# schematic.net
KiCad netlist of a schematic drawn in EAGLE
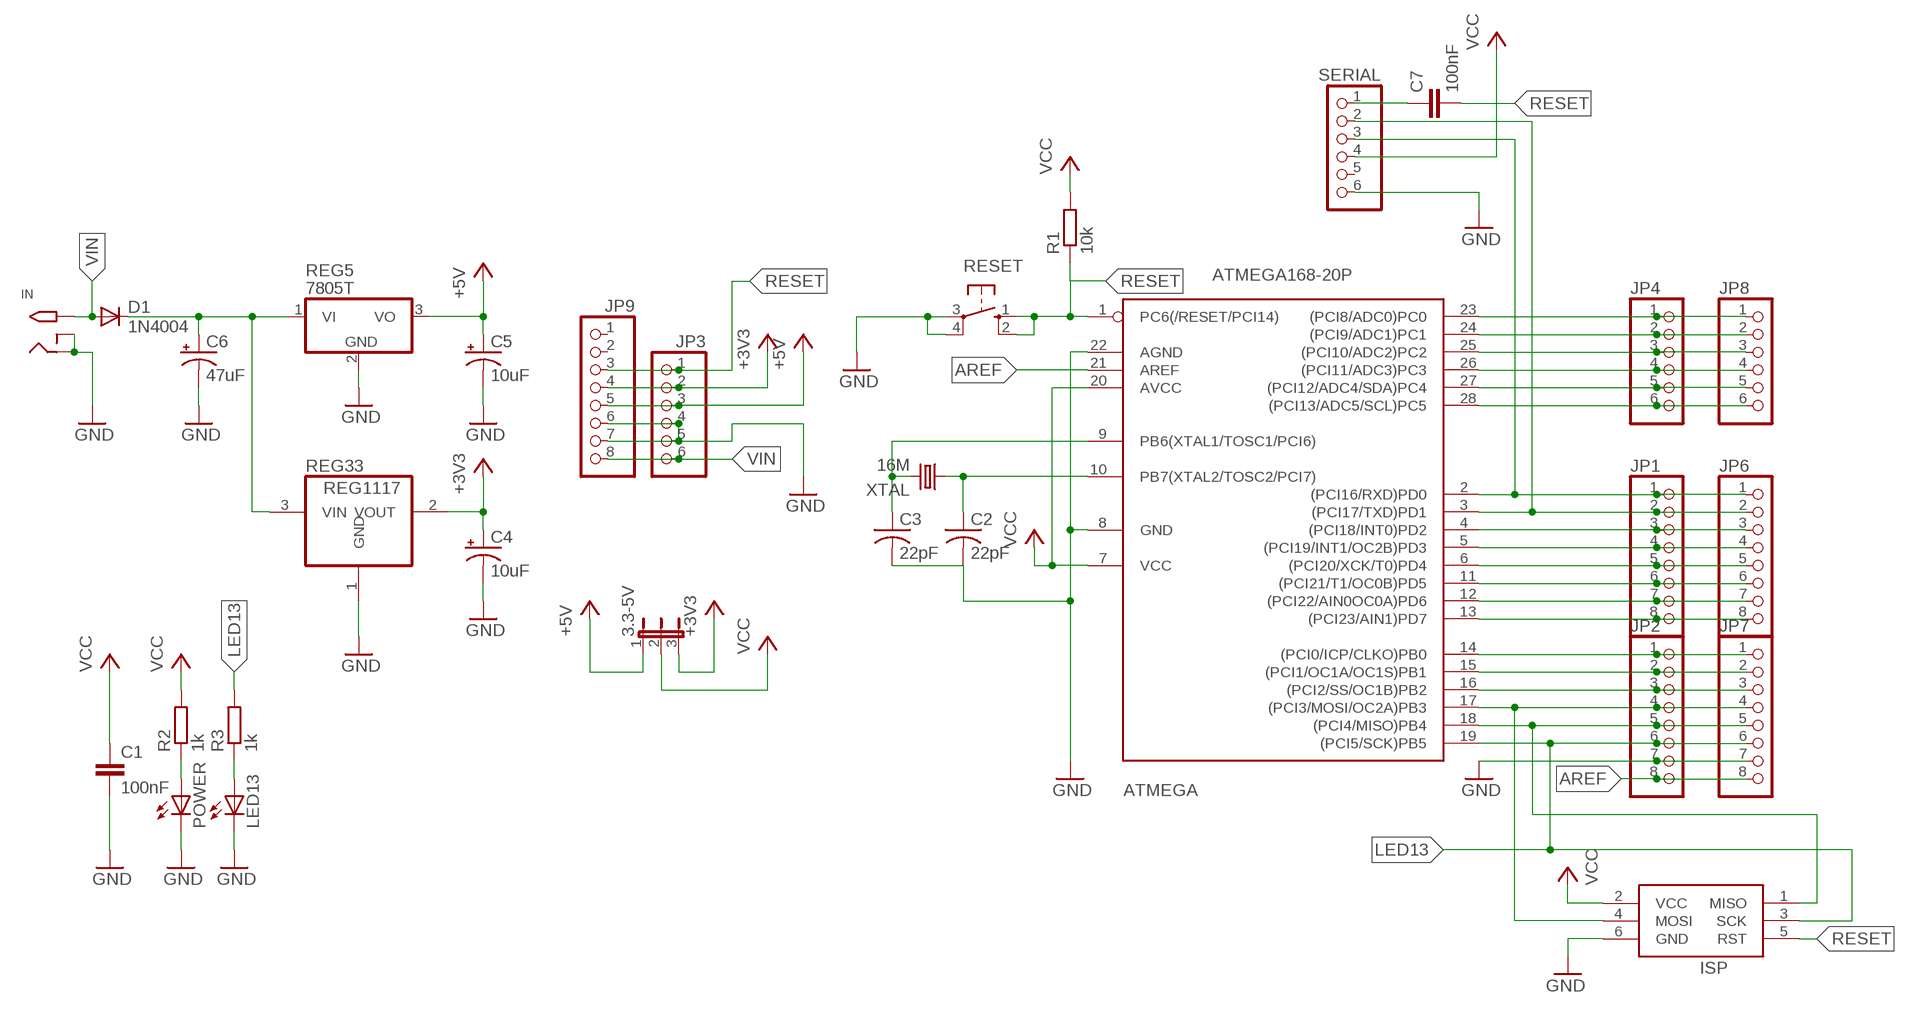
[diagram p0: schematic, sheet 1]

(export (version "E")
  (design (tool "Eeschema 10.0.6"))
  (components
    (comp (ref "3.3-5V")
      (value "JP2E")
      (footprint "eagle-import:JP2")
      (libsource (lib "eagle-import") (part "JP2E"))
    )
    (comp (ref "ATMEGA")
      (value "ATMEGA168-20P")
      (footprint "eagle-import:DIL28-3")
      (libsource (lib "eagle-import") (part "ATMEGA168P-20"))
    )
    (comp (ref "C1")
      (value "100nF")
      (footprint "eagle-import:C050-025X075")
      (libsource (lib "eagle-import") (part "C-EU050-025X075"))
    )
    (comp (ref "C2")
      (value "22pF")
      (footprint "eagle-import:C025-030X050")
      (libsource (lib "eagle-import") (part "C-US025-030X050"))
    )
    (comp (ref "C3")
      (value "22pF")
      (footprint "eagle-import:C025-030X050")
      (libsource (lib "eagle-import") (part "C-US025-030X050"))
    )
    (comp (ref "C4")
      (value "10uF")
      (footprint "eagle-import:E2,5-5")
      (libsource (lib "eagle-import") (part "CPOL-USE2.5-5"))
    )
    (comp (ref "C5")
      (value "10uF")
      (footprint "eagle-import:E2,5-5")
      (libsource (lib "eagle-import") (part "CPOL-USE2.5-5"))
    )
    (comp (ref "C6")
      (value "47uF")
      (footprint "eagle-import:E2,5-6")
      (libsource (lib "eagle-import") (part "CPOL-USE2.5-6"))
    )
    (comp (ref "C7")
      (value "100nF")
      (footprint "eagle-import:C050-025X075")
      (libsource (lib "eagle-import") (part "C-EU050-025X075"))
    )
    (comp (ref "D1")
      (value "1N4004")
      (footprint "eagle-import:DO41-10")
      (libsource (lib "eagle-import") (part "1N4004"))
    )
    (comp (ref "IN")
      (value "2.1MMJACKTHM")
      (footprint "eagle-import:PJ-102A")
      (libsource (lib "eagle-import") (part "2.1MMJACKTHM"))
    )
    (comp (ref "ISP")
      (value "AVRISP-6")
      (footprint "eagle-import:AVRISP")
      (libsource (lib "eagle-import") (part "AVRISP-6"))
    )
    (comp (ref "JP1")
      (value "PINHD-1X8BIG")
      (footprint "eagle-import:1X08-BIG")
      (libsource (lib "eagle-import") (part "PINHD-1X8BIG"))
    )
    (comp (ref "JP2")
      (value "PINHD-1X8BIG")
      (footprint "eagle-import:1X08-BIG")
      (libsource (lib "eagle-import") (part "PINHD-1X8BIG"))
    )
    (comp (ref "JP3")
      (value "PINHD-1X6B")
      (footprint "eagle-import:1X06-BIG")
      (libsource (lib "eagle-import") (part "PINHD-1X6B"))
    )
    (comp (ref "JP4")
      (value "PINHD-1X6B")
      (footprint "eagle-import:1X06-BIG")
      (libsource (lib "eagle-import") (part "PINHD-1X6B"))
    )
    (comp (ref "JP6")
      (value "PINHD-1X8BIG")
      (footprint "eagle-import:1X08-BIG")
      (libsource (lib "eagle-import") (part "PINHD-1X8BIG"))
    )
    (comp (ref "JP7")
      (value "PINHD-1X8BIG")
      (footprint "eagle-import:1X08-BIG")
      (libsource (lib "eagle-import") (part "PINHD-1X8BIG"))
    )
    (comp (ref "JP8")
      (value "PINHD-1X6B")
      (footprint "eagle-import:1X06-BIG")
      (libsource (lib "eagle-import") (part "PINHD-1X6B"))
    )
    (comp (ref "JP9")
      (value "PINHD-1X8BIG")
      (footprint "eagle-import:1X08-BIG")
      (libsource (lib "eagle-import") (part "PINHD-1X8BIG"))
    )
    (comp (ref "LED13")
      (value "LED3MM")
      (footprint "eagle-import:LED3MM")
      (libsource (lib "eagle-import") (part "LED3MM"))
    )
    (comp (ref "POWER")
      (value "LED3MM")
      (footprint "eagle-import:LED3MM")
      (libsource (lib "eagle-import") (part "LED3MM"))
    )
    (comp (ref "R1")
      (value "10k")
      (footprint "eagle-import:0207_7")
      (libsource (lib "eagle-import") (part "R-EU_0207/7"))
    )
    (comp (ref "R2")
      (value "1k")
      (footprint "eagle-import:0207_7")
      (libsource (lib "eagle-import") (part "R-EU_0207/7"))
    )
    (comp (ref "R3")
      (value "1k")
      (footprint "eagle-import:0207_7")
      (libsource (lib "eagle-import") (part "R-EU_0207/7"))
    )
    (comp (ref "REG5")
      (value "7805T")
      (footprint "eagle-import:TO220H")
      (libsource (lib "eagle-import") (part "78T05"))
    )
    (comp (ref "REG33")
      (value "REG1117")
      (footprint "eagle-import:SOT223")
      (libsource (lib "eagle-import") (part "REG1117"))
    )
    (comp (ref "RESET")
      (value "10-XX")
      (footprint "eagle-import:B3F-10XX")
      (fields (field (name "MPN") "B3F-1000"))
      (libsource (lib "eagle-import") (part "10-XX"))
    )
    (comp (ref "SERIAL")
      (value "PINHD-1X6")
      (footprint "eagle-import:1X06")
      (libsource (lib "eagle-import") (part "PINHD-1X6"))
    )
    (comp (ref "XTAL")
      (value "16M")
      (footprint "eagle-import:HC49_S")
      (libsource (lib "eagle-import") (part "CRYSTALHC49S"))
    )
  )
  (nets
    (net (code "1") (name "+3V3") (class "Default")
      (node (ref "3.3-5V") (pin "3") (pinfunction "3_3") (pintype "passive"))
      (node (ref "C4") (pin "+") (pinfunction "+_+") (pintype "passive"))
      (node (ref "JP3") (pin "2") (pinfunction "2_2") (pintype "passive"))
      (node (ref "JP9") (pin "4") (pinfunction "4_4") (pintype "passive"))
      (node (ref "REG33") (pin "2") (pinfunction "VOUT_2") (pintype "output"))
    )
    (net (code "2") (name "+5V") (class "Default")
      (node (ref "3.3-5V") (pin "1") (pinfunction "1_1") (pintype "passive"))
      (node (ref "C5") (pin "+") (pinfunction "+_+") (pintype "passive"))
      (node (ref "JP3") (pin "3") (pinfunction "3_3") (pintype "passive"))
      (node (ref "JP9") (pin "5") (pinfunction "5_5") (pintype "passive"))
      (node (ref "REG5") (pin "3") (pinfunction "VO_3") (pintype "passive"))
    )
    (net (code "3") (name "AREF") (class "Default")
      (node (ref "ATMEGA") (pin "21") (pinfunction "AREF_21") (pintype "bidirectional"))
      (node (ref "JP2") (pin "8") (pinfunction "8_8") (pintype "passive"))
      (node (ref "JP7") (pin "8") (pinfunction "8_8") (pintype "passive"))
    )
    (net (code "4") (name "GND") (class "Default")
      (node (ref "ATMEGA") (pin "22") (pinfunction "AGND_22") (pintype "bidirectional"))
      (node (ref "ATMEGA") (pin "8") (pinfunction "GND_8") (pintype "bidirectional"))
      (node (ref "C1") (pin "2") (pinfunction "2_2") (pintype "passive"))
      (node (ref "C2") (pin "2") (pinfunction "2_2") (pintype "passive"))
      (node (ref "C3") (pin "2") (pinfunction "2_2") (pintype "passive"))
      (node (ref "C4") (pin "-") (pinfunction "-_-") (pintype "passive"))
      (node (ref "C5") (pin "-") (pinfunction "-_-") (pintype "passive"))
      (node (ref "C6") (pin "-") (pinfunction "-_-") (pintype "passive"))
      (node (ref "IN") (pin "RING") (pinfunction "RING_RING") (pintype "bidirectional"))
      (node (ref "IN") (pin "RING_SW") (pinfunction "RING_SW_RING_SW") (pintype "bidirectional"))
      (node (ref "ISP") (pin "6") (pinfunction "GND_6") (pintype "power_in"))
      (node (ref "JP2") (pin "7") (pinfunction "7_7") (pintype "passive"))
      (node (ref "JP3") (pin "4") (pinfunction "4_4") (pintype "passive"))
      (node (ref "JP3") (pin "5") (pinfunction "5_5") (pintype "passive"))
      (node (ref "JP7") (pin "7") (pinfunction "7_7") (pintype "passive"))
      (node (ref "JP9") (pin "6") (pinfunction "6_6") (pintype "passive"))
      (node (ref "JP9") (pin "7") (pinfunction "7_7") (pintype "passive"))
      (node (ref "LED13") (pin "K") (pinfunction "C_K") (pintype "passive"))
      (node (ref "POWER") (pin "K") (pinfunction "C_K") (pintype "passive"))
      (node (ref "REG33") (pin "1") (pinfunction "GND_1") (pintype "power_in"))
      (node (ref "REG5") (pin "2") (pinfunction "GND_2") (pintype "passive"))
      (node (ref "RESET") (pin "3") (pinfunction "P_3") (pintype "passive"))
      (node (ref "RESET") (pin "4") (pinfunction "P1_4") (pintype "passive"))
      (node (ref "SERIAL") (pin "6") (pinfunction "6_6") (pintype "passive"))
    )
    (net (code "5") (name "LED13") (class "Default")
      (node (ref "ATMEGA") (pin "19") (pinfunction "(PCI5/SCK)PB5_19") (pintype "bidirectional"))
      (node (ref "ISP") (pin "3") (pinfunction "SCK_3") (pintype "output"))
      (node (ref "JP2") (pin "6") (pinfunction "6_6") (pintype "passive"))
      (node (ref "JP7") (pin "6") (pinfunction "6_6") (pintype "passive"))
      (node (ref "R3") (pin "2") (pinfunction "2_2") (pintype "passive"))
    )
    (net (code "6") (name "Net-(ATMEGA-(PCI0{slash}ICP{slash}CLKO)PB0)") (class "Default")
      (node (ref "ATMEGA") (pin "14") (pinfunction "(PCI0/ICP/CLKO)PB0_14") (pintype "bidirectional"))
      (node (ref "JP2") (pin "1") (pinfunction "1_1") (pintype "passive"))
      (node (ref "JP7") (pin "1") (pinfunction "1_1") (pintype "passive"))
    )
    (net (code "7") (name "Net-(ATMEGA-(PCI1{slash}OC1A{slash}OC1S)PB1)") (class "Default")
      (node (ref "ATMEGA") (pin "15") (pinfunction "(PCI1/OC1A/OC1S)PB1_15") (pintype "bidirectional"))
      (node (ref "JP2") (pin "2") (pinfunction "2_2") (pintype "passive"))
      (node (ref "JP7") (pin "2") (pinfunction "2_2") (pintype "passive"))
    )
    (net (code "8") (name "Net-(ATMEGA-(PCI2{slash}SS{slash}OC1B)PB2)") (class "Default")
      (node (ref "ATMEGA") (pin "16") (pinfunction "(PCI2/SS/OC1B)PB2_16") (pintype "bidirectional"))
      (node (ref "JP2") (pin "3") (pinfunction "3_3") (pintype "passive"))
      (node (ref "JP7") (pin "3") (pinfunction "3_3") (pintype "passive"))
    )
    (net (code "9") (name "Net-(ATMEGA-(PCI3{slash}MOSI{slash}OC2A)PB3)") (class "Default")
      (node (ref "ATMEGA") (pin "17") (pinfunction "(PCI3/MOSI/OC2A)PB3_17") (pintype "bidirectional"))
      (node (ref "ISP") (pin "4") (pinfunction "MOSI_4") (pintype "output"))
      (node (ref "JP2") (pin "4") (pinfunction "4_4") (pintype "passive"))
      (node (ref "JP7") (pin "4") (pinfunction "4_4") (pintype "passive"))
    )
    (net (code "10") (name "Net-(ATMEGA-(PCI4{slash}MISO)PB4)") (class "Default")
      (node (ref "ATMEGA") (pin "18") (pinfunction "(PCI4/MISO)PB4_18") (pintype "bidirectional"))
      (node (ref "ISP") (pin "1") (pinfunction "MISO_1") (pintype "input"))
      (node (ref "JP2") (pin "5") (pinfunction "5_5") (pintype "passive"))
      (node (ref "JP7") (pin "5") (pinfunction "5_5") (pintype "passive"))
    )
    (net (code "11") (name "Net-(ATMEGA-(PCI8{slash}ADC0)PC0)") (class "Default")
      (node (ref "ATMEGA") (pin "23") (pinfunction "(PCI8/ADC0)PC0_23") (pintype "bidirectional"))
      (node (ref "JP4") (pin "1") (pinfunction "1_1") (pintype "passive"))
      (node (ref "JP8") (pin "1") (pinfunction "1_1") (pintype "passive"))
    )
    (net (code "12") (name "Net-(ATMEGA-(PCI9{slash}ADC1)PC1)") (class "Default")
      (node (ref "ATMEGA") (pin "24") (pinfunction "(PCI9/ADC1)PC1_24") (pintype "bidirectional"))
      (node (ref "JP4") (pin "2") (pinfunction "2_2") (pintype "passive"))
      (node (ref "JP8") (pin "2") (pinfunction "2_2") (pintype "passive"))
    )
    (net (code "13") (name "Net-(ATMEGA-(PCI10{slash}ADC2)PC2)") (class "Default")
      (node (ref "ATMEGA") (pin "25") (pinfunction "(PCI10/ADC2)PC2_25") (pintype "bidirectional"))
      (node (ref "JP4") (pin "3") (pinfunction "3_3") (pintype "passive"))
      (node (ref "JP8") (pin "3") (pinfunction "3_3") (pintype "passive"))
    )
    (net (code "14") (name "Net-(ATMEGA-(PCI11{slash}ADC3)PC3)") (class "Default")
      (node (ref "ATMEGA") (pin "26") (pinfunction "(PCI11/ADC3)PC3_26") (pintype "bidirectional"))
      (node (ref "JP4") (pin "4") (pinfunction "4_4") (pintype "passive"))
      (node (ref "JP8") (pin "4") (pinfunction "4_4") (pintype "passive"))
    )
    (net (code "15") (name "Net-(ATMEGA-(PCI12{slash}ADC4{slash}SDA)PC4)") (class "Default")
      (node (ref "ATMEGA") (pin "27") (pinfunction "(PCI12/ADC4/SDA)PC4_27") (pintype "bidirectional"))
      (node (ref "JP4") (pin "5") (pinfunction "5_5") (pintype "passive"))
      (node (ref "JP8") (pin "5") (pinfunction "5_5") (pintype "passive"))
    )
    (net (code "16") (name "Net-(ATMEGA-(PCI13{slash}ADC5{slash}SCL)PC5)") (class "Default")
      (node (ref "ATMEGA") (pin "28") (pinfunction "(PCI13/ADC5/SCL)PC5_28") (pintype "bidirectional"))
      (node (ref "JP4") (pin "6") (pinfunction "6_6") (pintype "passive"))
      (node (ref "JP8") (pin "6") (pinfunction "6_6") (pintype "passive"))
    )
    (net (code "17") (name "Net-(ATMEGA-(PCI16{slash}RXD)PD0)") (class "Default")
      (node (ref "ATMEGA") (pin "2") (pinfunction "(PCI16/RXD)PD0_2") (pintype "bidirectional"))
      (node (ref "JP1") (pin "1") (pinfunction "1_1") (pintype "passive"))
      (node (ref "JP6") (pin "1") (pinfunction "1_1") (pintype "passive"))
      (node (ref "SERIAL") (pin "3") (pinfunction "3_3") (pintype "passive"))
    )
    (net (code "18") (name "Net-(ATMEGA-(PCI17{slash}TXD)PD1)") (class "Default")
      (node (ref "ATMEGA") (pin "3") (pinfunction "(PCI17/TXD)PD1_3") (pintype "bidirectional"))
      (node (ref "JP1") (pin "2") (pinfunction "2_2") (pintype "passive"))
      (node (ref "JP6") (pin "2") (pinfunction "2_2") (pintype "passive"))
      (node (ref "SERIAL") (pin "2") (pinfunction "2_2") (pintype "passive"))
    )
    (net (code "19") (name "Net-(ATMEGA-(PCI18{slash}INT0)PD2)") (class "Default")
      (node (ref "ATMEGA") (pin "4") (pinfunction "(PCI18/INT0)PD2_4") (pintype "bidirectional"))
      (node (ref "JP1") (pin "3") (pinfunction "3_3") (pintype "passive"))
      (node (ref "JP6") (pin "3") (pinfunction "3_3") (pintype "passive"))
    )
    (net (code "20") (name "Net-(ATMEGA-(PCI19{slash}INT1{slash}OC2B)PD3)") (class "Default")
      (node (ref "ATMEGA") (pin "5") (pinfunction "(PCI19/INT1/OC2B)PD3_5") (pintype "bidirectional"))
      (node (ref "JP1") (pin "4") (pinfunction "4_4") (pintype "passive"))
      (node (ref "JP6") (pin "4") (pinfunction "4_4") (pintype "passive"))
    )
    (net (code "21") (name "Net-(ATMEGA-(PCI20{slash}XCK{slash}T0)PD4)") (class "Default")
      (node (ref "ATMEGA") (pin "6") (pinfunction "(PCI20/XCK/T0)PD4_6") (pintype "bidirectional"))
      (node (ref "JP1") (pin "5") (pinfunction "5_5") (pintype "passive"))
      (node (ref "JP6") (pin "5") (pinfunction "5_5") (pintype "passive"))
    )
    (net (code "22") (name "Net-(ATMEGA-(PCI21{slash}T1{slash}OC0B)PD5)") (class "Default")
      (node (ref "ATMEGA") (pin "11") (pinfunction "(PCI21/T1/OC0B)PD5_11") (pintype "bidirectional"))
      (node (ref "JP1") (pin "6") (pinfunction "6_6") (pintype "passive"))
      (node (ref "JP6") (pin "6") (pinfunction "6_6") (pintype "passive"))
    )
    (net (code "23") (name "Net-(ATMEGA-(PCI22{slash}AIN0OC0A)PD6)") (class "Default")
      (node (ref "ATMEGA") (pin "12") (pinfunction "(PCI22/AIN0OC0A)PD6_12") (pintype "bidirectional"))
      (node (ref "JP1") (pin "7") (pinfunction "7_7") (pintype "passive"))
      (node (ref "JP6") (pin "7") (pinfunction "7_7") (pintype "passive"))
    )
    (net (code "24") (name "Net-(ATMEGA-(PCI23{slash}AIN1)PD7)") (class "Default")
      (node (ref "ATMEGA") (pin "13") (pinfunction "(PCI23/AIN1)PD7_13") (pintype "bidirectional"))
      (node (ref "JP1") (pin "8") (pinfunction "8_8") (pintype "passive"))
      (node (ref "JP6") (pin "8") (pinfunction "8_8") (pintype "passive"))
    )
    (net (code "25") (name "Net-(ATMEGA-PB6(XTAL1{slash}TOSC1{slash}PCI6))") (class "Default")
      (node (ref "ATMEGA") (pin "9") (pinfunction "PB6(XTAL1/TOSC1/PCI6)_9") (pintype "bidirectional"))
      (node (ref "C3") (pin "1") (pinfunction "1_1") (pintype "passive"))
      (node (ref "XTAL") (pin "2") (pinfunction "2_2") (pintype "passive"))
    )
    (net (code "26") (name "Net-(ATMEGA-PB7(XTAL2{slash}TOSC2{slash}PCI7))") (class "Default")
      (node (ref "ATMEGA") (pin "10") (pinfunction "PB7(XTAL2/TOSC2/PCI7)_10") (pintype "bidirectional"))
      (node (ref "C2") (pin "1") (pinfunction "1_1") (pintype "passive"))
      (node (ref "XTAL") (pin "1") (pinfunction "1_1") (pintype "passive"))
    )
    (net (code "27") (name "Net-(C7-Pad1)") (class "Default")
      (node (ref "C7") (pin "1") (pinfunction "1_1") (pintype "passive"))
      (node (ref "SERIAL") (pin "1") (pinfunction "1_1") (pintype "passive"))
    )
    (net (code "28") (name "Net-(LED13-PadA)") (class "Default")
      (node (ref "LED13") (pin "A") (pinfunction "A_A") (pintype "passive"))
      (node (ref "R3") (pin "1") (pinfunction "1_1") (pintype "passive"))
    )
    (net (code "29") (name "Net-(POWER-PadA)") (class "Default")
      (node (ref "POWER") (pin "A") (pinfunction "A_A") (pintype "passive"))
      (node (ref "R2") (pin "1") (pinfunction "1_1") (pintype "passive"))
    )
    (net (code "30") (name "Net-(REG33-VIN)") (class "Default")
      (node (ref "C6") (pin "+") (pinfunction "+_+") (pintype "passive"))
      (node (ref "D1") (pin "C") (pinfunction "C_C") (pintype "passive"))
      (node (ref "REG33") (pin "3") (pinfunction "VIN_3") (pintype "input"))
      (node (ref "REG5") (pin "1") (pinfunction "VI_1") (pintype "input"))
    )
    (net (code "31") (name "RESET") (class "Default")
      (node (ref "ATMEGA") (pin "1") (pinfunction "PC6(/RESET/PCI14)_1") (pintype "bidirectional"))
      (node (ref "C7") (pin "2") (pinfunction "2_2") (pintype "passive"))
      (node (ref "ISP") (pin "5") (pinfunction "RST_5") (pintype "output"))
      (node (ref "JP3") (pin "1") (pinfunction "1_1") (pintype "passive"))
      (node (ref "JP9") (pin "3") (pinfunction "3_3") (pintype "passive"))
      (node (ref "R1") (pin "1") (pinfunction "1_1") (pintype "passive"))
      (node (ref "RESET") (pin "1") (pinfunction "S_1") (pintype "passive"))
      (node (ref "RESET") (pin "2") (pinfunction "S1_2") (pintype "passive"))
    )
    (net (code "32") (name "VCC") (class "Default")
      (node (ref "3.3-5V") (pin "2") (pinfunction "2_2") (pintype "passive"))
      (node (ref "ATMEGA") (pin "20") (pinfunction "AVCC_20") (pintype "bidirectional"))
      (node (ref "ATMEGA") (pin "7") (pinfunction "VCC_7") (pintype "bidirectional"))
      (node (ref "C1") (pin "1") (pinfunction "1_1") (pintype "passive"))
      (node (ref "ISP") (pin "2") (pinfunction "VCC_2") (pintype "power_in"))
      (node (ref "R1") (pin "2") (pinfunction "2_2") (pintype "passive"))
      (node (ref "R2") (pin "2") (pinfunction "2_2") (pintype "passive"))
      (node (ref "SERIAL") (pin "4") (pinfunction "4_4") (pintype "passive"))
    )
    (net (code "33") (name "VIN") (class "Default")
      (node (ref "D1") (pin "A") (pinfunction "A_A") (pintype "passive"))
      (node (ref "IN") (pin "TIP") (pinfunction "TIP_TIP") (pintype "bidirectional"))
      (node (ref "JP3") (pin "6") (pinfunction "6_6") (pintype "passive"))
      (node (ref "JP9") (pin "8") (pinfunction "8_8") (pintype "passive"))
    )
    (net (code "34") (name "unconnected-(JP9-Pad1)") (class "Default")
      (node (ref "JP9") (pin "1") (pinfunction "1_1") (pintype "passive"))
    )
    (net (code "35") (name "unconnected-(JP9-Pad2)") (class "Default")
      (node (ref "JP9") (pin "2") (pinfunction "2_2") (pintype "passive"))
    )
    (net (code "36") (name "unconnected-(SERIAL-Pad5)") (class "Default")
      (node (ref "SERIAL") (pin "5") (pinfunction "5_5") (pintype "passive"))
    )
  )
)
